# circuit.net
KiCad netlist of a schematic drawn in EAGLE
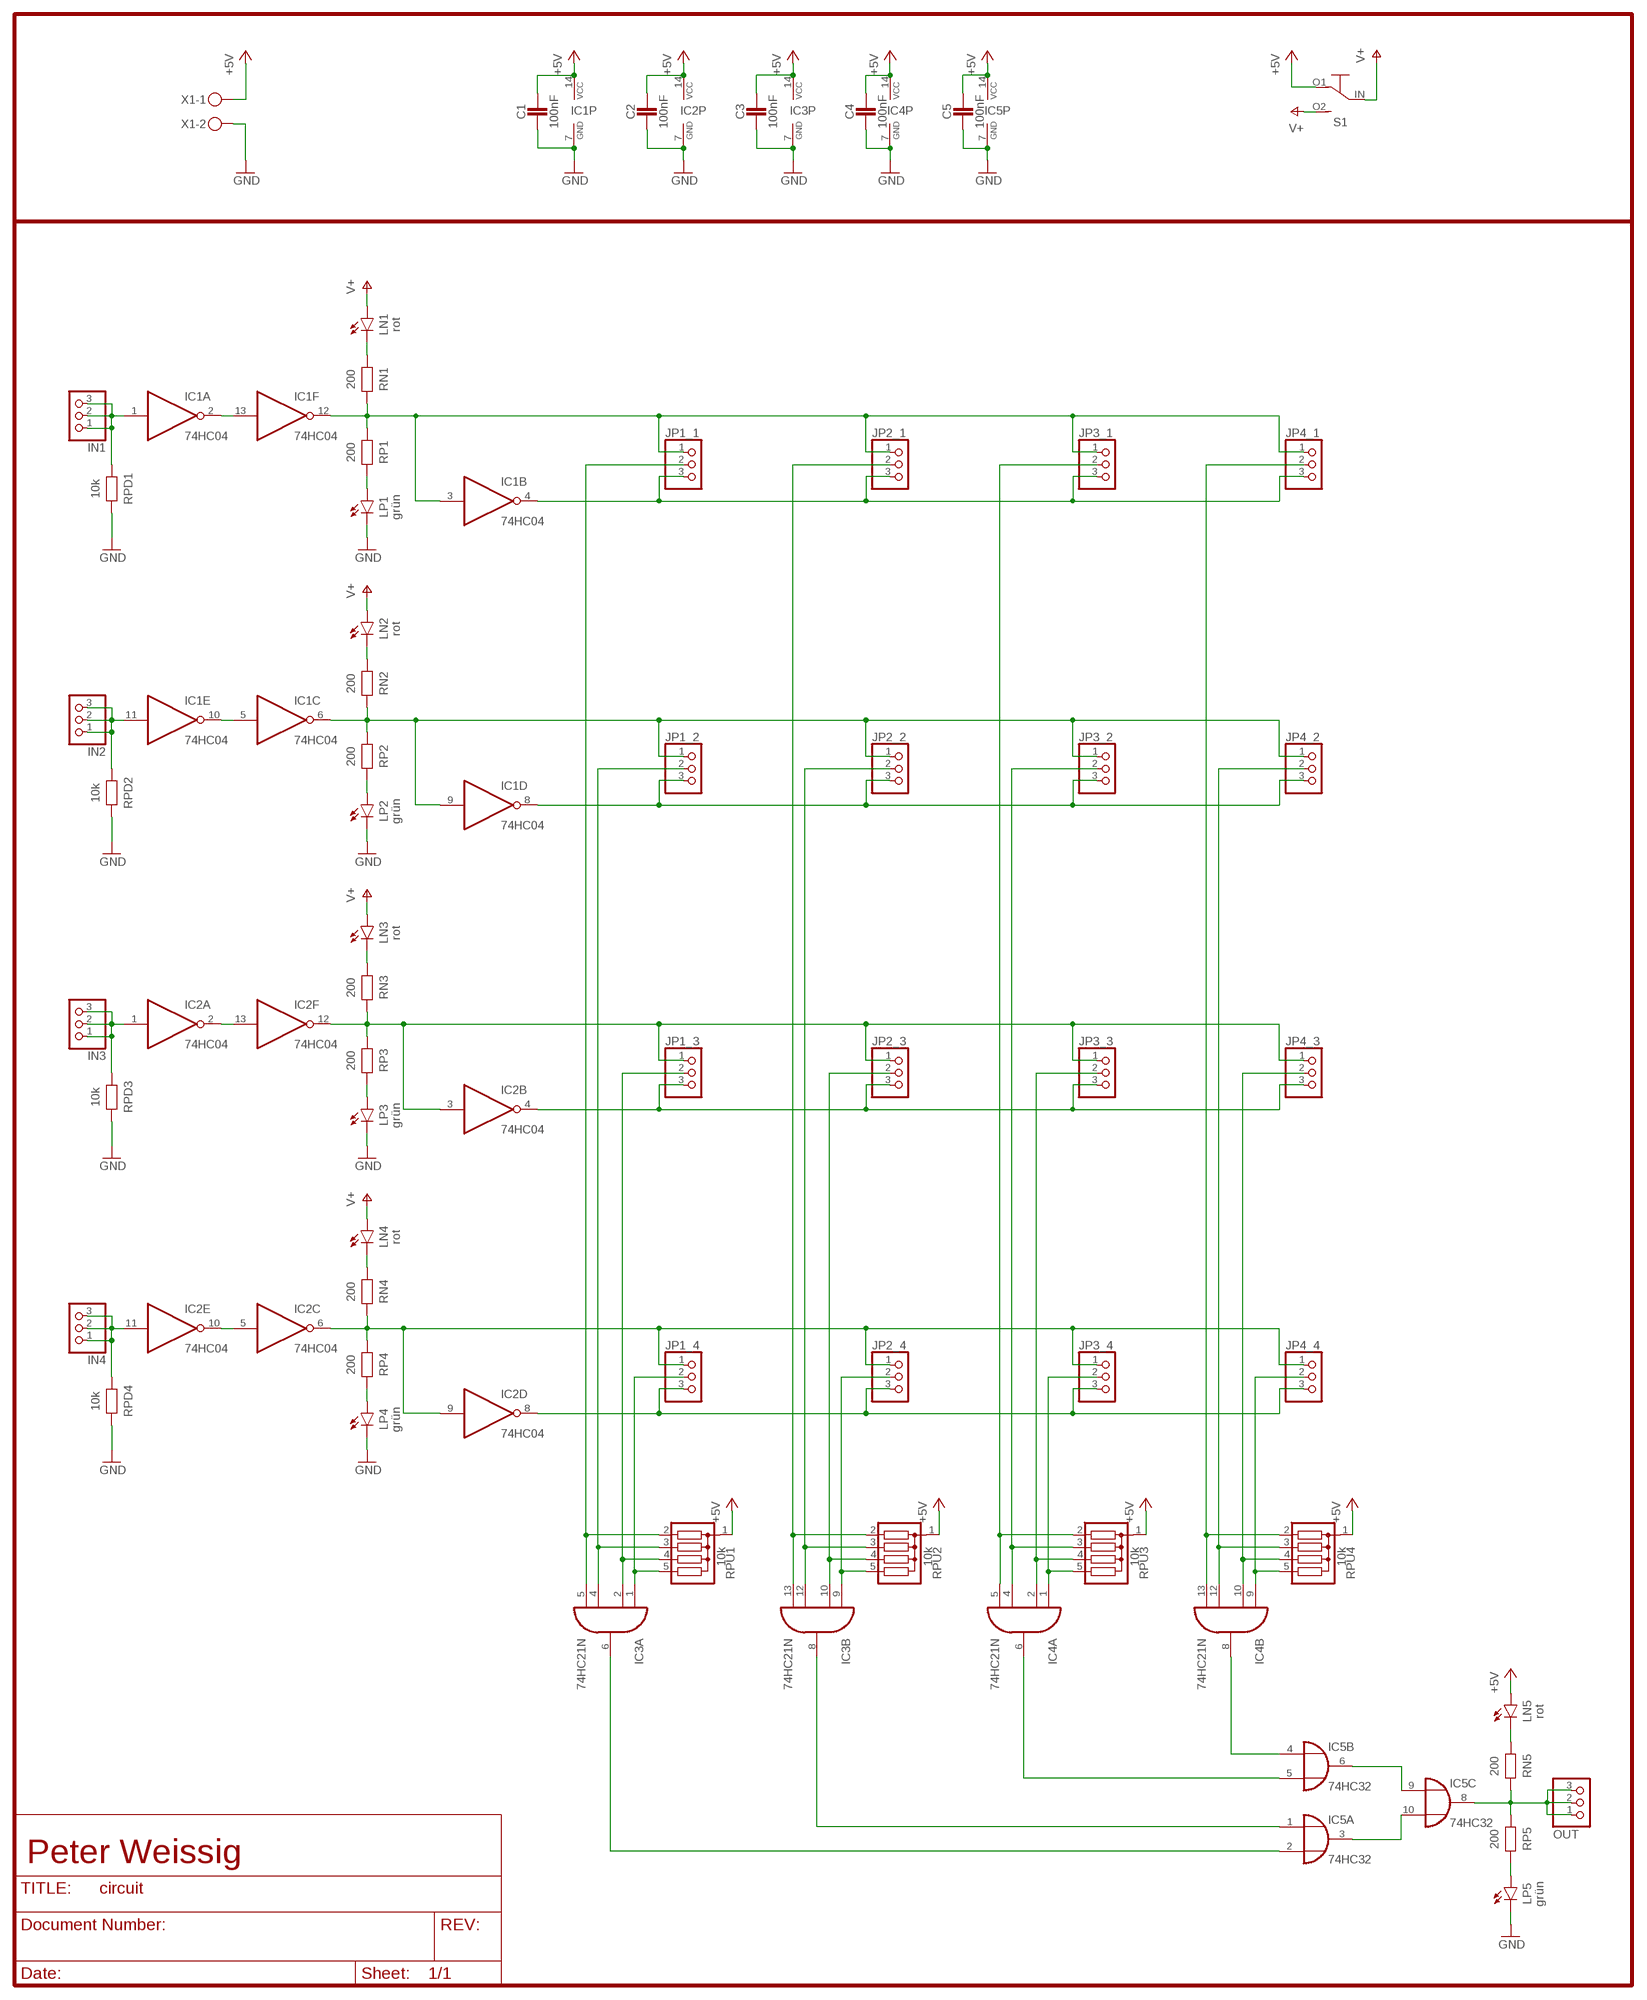
[diagram p0: schematic, sheet 1]

(export (version "E")
  (design (tool "Eeschema 10.0.6"))
  (components
    (comp (ref "C1")
      (value "100nF")
      (footprint "eagle-import:C_THT_2")
      (libsource (lib "eagle-import") (part "CAPACITATOR-2,5MM"))
    )
    (comp (ref "C2")
      (value "100nF")
      (footprint "eagle-import:C_THT_2")
      (libsource (lib "eagle-import") (part "CAPACITATOR-2,5MM"))
    )
    (comp (ref "C3")
      (value "100nF")
      (footprint "eagle-import:C_THT_3")
      (libsource (lib "eagle-import") (part "CAPACITATOR-5MM"))
    )
    (comp (ref "C4")
      (value "100nF")
      (footprint "eagle-import:C_THT_3")
      (libsource (lib "eagle-import") (part "CAPACITATOR-5MM"))
    )
    (comp (ref "C5")
      (value "100nF")
      (footprint "eagle-import:C_THT_2")
      (libsource (lib "eagle-import") (part "CAPACITATOR-2,5MM"))
    )
    (comp (ref "IC1")
      (value "74HC04")
      (footprint "eagle-import:DIL14")
      (libsource (lib "eagle-import") (part "7404NAC"))
    )
    (comp (ref "IC2")
      (value "74HC04")
      (footprint "eagle-import:DIL14")
      (libsource (lib "eagle-import") (part "7404NAC"))
    )
    (comp (ref "IC3")
      (value "74HC21N")
      (footprint "eagle-import:DIL14")
      (libsource (lib "eagle-import") (part "7421NHC"))
    )
    (comp (ref "IC4")
      (value "74HC21N")
      (footprint "eagle-import:DIL14")
      (libsource (lib "eagle-import") (part "7421NHC"))
    )
    (comp (ref "IC5")
      (value "74HC32")
      (footprint "eagle-import:DIL14")
      (libsource (lib "eagle-import") (part "7432NAC"))
    )
    (comp (ref "IN1")
      (value "PINHD-1X3")
      (footprint "eagle-import:1X03")
      (libsource (lib "eagle-import") (part "PINHD-1X3"))
    )
    (comp (ref "IN2")
      (value "PINHD-1X3")
      (footprint "eagle-import:1X03")
      (libsource (lib "eagle-import") (part "PINHD-1X3"))
    )
    (comp (ref "IN3")
      (value "PINHD-1X3")
      (footprint "eagle-import:1X03")
      (libsource (lib "eagle-import") (part "PINHD-1X3"))
    )
    (comp (ref "IN4")
      (value "PINHD-1X3")
      (footprint "eagle-import:1X03")
      (libsource (lib "eagle-import") (part "PINHD-1X3"))
    )
    (comp (ref "JP1_1")
      (value "PINHD-1X3")
      (footprint "eagle-import:1X03")
      (libsource (lib "eagle-import") (part "PINHD-1X3"))
    )
    (comp (ref "JP1_2")
      (value "PINHD-1X3")
      (footprint "eagle-import:1X03")
      (libsource (lib "eagle-import") (part "PINHD-1X3"))
    )
    (comp (ref "JP1_3")
      (value "PINHD-1X3")
      (footprint "eagle-import:1X03")
      (libsource (lib "eagle-import") (part "PINHD-1X3"))
    )
    (comp (ref "JP1_4")
      (value "PINHD-1X3")
      (footprint "eagle-import:1X03")
      (libsource (lib "eagle-import") (part "PINHD-1X3"))
    )
    (comp (ref "JP2_1")
      (value "PINHD-1X3")
      (footprint "eagle-import:1X03")
      (libsource (lib "eagle-import") (part "PINHD-1X3"))
    )
    (comp (ref "JP2_2")
      (value "PINHD-1X3")
      (footprint "eagle-import:1X03")
      (libsource (lib "eagle-import") (part "PINHD-1X3"))
    )
    (comp (ref "JP2_3")
      (value "PINHD-1X3")
      (footprint "eagle-import:1X03")
      (libsource (lib "eagle-import") (part "PINHD-1X3"))
    )
    (comp (ref "JP2_4")
      (value "PINHD-1X3")
      (footprint "eagle-import:1X03")
      (libsource (lib "eagle-import") (part "PINHD-1X3"))
    )
    (comp (ref "JP3_1")
      (value "PINHD-1X3")
      (footprint "eagle-import:1X03")
      (libsource (lib "eagle-import") (part "PINHD-1X3"))
    )
    (comp (ref "JP3_2")
      (value "PINHD-1X3")
      (footprint "eagle-import:1X03")
      (libsource (lib "eagle-import") (part "PINHD-1X3"))
    )
    (comp (ref "JP3_3")
      (value "PINHD-1X3")
      (footprint "eagle-import:1X03")
      (libsource (lib "eagle-import") (part "PINHD-1X3"))
    )
    (comp (ref "JP3_4")
      (value "PINHD-1X3")
      (footprint "eagle-import:1X03")
      (libsource (lib "eagle-import") (part "PINHD-1X3"))
    )
    (comp (ref "JP4_1")
      (value "PINHD-1X3")
      (footprint "eagle-import:1X03")
      (libsource (lib "eagle-import") (part "PINHD-1X3"))
    )
    (comp (ref "JP4_2")
      (value "PINHD-1X3")
      (footprint "eagle-import:1X03")
      (libsource (lib "eagle-import") (part "PINHD-1X3"))
    )
    (comp (ref "JP4_3")
      (value "PINHD-1X3")
      (footprint "eagle-import:1X03")
      (libsource (lib "eagle-import") (part "PINHD-1X3"))
    )
    (comp (ref "JP4_4")
      (value "PINHD-1X3")
      (footprint "eagle-import:1X03")
      (libsource (lib "eagle-import") (part "PINHD-1X3"))
    )
    (comp (ref "LN1")
      (value "rot")
      (footprint "eagle-import:LED_3MM")
      (libsource (lib "eagle-import") (part "LED-3MM"))
    )
    (comp (ref "LN2")
      (value "rot")
      (footprint "eagle-import:LED_3MM")
      (libsource (lib "eagle-import") (part "LED-3MM"))
    )
    (comp (ref "LN3")
      (value "rot")
      (footprint "eagle-import:LED_3MM")
      (libsource (lib "eagle-import") (part "LED-3MM"))
    )
    (comp (ref "LN4")
      (value "rot")
      (footprint "eagle-import:LED_3MM")
      (libsource (lib "eagle-import") (part "LED-3MM"))
    )
    (comp (ref "LN5")
      (value "rot")
      (footprint "eagle-import:LED_3MM")
      (libsource (lib "eagle-import") (part "LED-3MM"))
    )
    (comp (ref "LP1")
      (value "grün")
      (footprint "eagle-import:LED_3MM")
      (libsource (lib "eagle-import") (part "LED-3MM"))
    )
    (comp (ref "LP2")
      (value "grün")
      (footprint "eagle-import:LED_3MM")
      (libsource (lib "eagle-import") (part "LED-3MM"))
    )
    (comp (ref "LP3")
      (value "grün")
      (footprint "eagle-import:LED_3MM")
      (libsource (lib "eagle-import") (part "LED-3MM"))
    )
    (comp (ref "LP4")
      (value "grün")
      (footprint "eagle-import:LED_3MM")
      (libsource (lib "eagle-import") (part "LED-3MM"))
    )
    (comp (ref "LP5")
      (value "grün")
      (footprint "eagle-import:LED_3MM")
      (libsource (lib "eagle-import") (part "LED-3MM"))
    )
    (comp (ref "OUT")
      (value "PINHD-1X3")
      (footprint "eagle-import:1X03")
      (libsource (lib "eagle-import") (part "PINHD-1X3"))
    )
    (comp (ref "RN1")
      (value "200")
      (footprint "eagle-import:R_THT_4")
      (libsource (lib "eagle-import") (part "RESISTOR-10MM"))
    )
    (comp (ref "RN2")
      (value "200")
      (footprint "eagle-import:R_THT_4")
      (libsource (lib "eagle-import") (part "RESISTOR-10MM"))
    )
    (comp (ref "RN3")
      (value "200")
      (footprint "eagle-import:R_THT_4")
      (libsource (lib "eagle-import") (part "RESISTOR-10MM"))
    )
    (comp (ref "RN4")
      (value "200")
      (footprint "eagle-import:R_THT_4")
      (libsource (lib "eagle-import") (part "RESISTOR-10MM"))
    )
    (comp (ref "RN5")
      (value "200")
      (footprint "eagle-import:R_THT_4")
      (libsource (lib "eagle-import") (part "RESISTOR-10MM"))
    )
    (comp (ref "RP1")
      (value "200")
      (footprint "eagle-import:R_THT_4")
      (libsource (lib "eagle-import") (part "RESISTOR-10MM"))
    )
    (comp (ref "RP2")
      (value "200")
      (footprint "eagle-import:R_THT_4")
      (libsource (lib "eagle-import") (part "RESISTOR-10MM"))
    )
    (comp (ref "RP3")
      (value "200")
      (footprint "eagle-import:R_THT_4")
      (libsource (lib "eagle-import") (part "RESISTOR-10MM"))
    )
    (comp (ref "RP4")
      (value "200")
      (footprint "eagle-import:R_THT_4")
      (libsource (lib "eagle-import") (part "RESISTOR-10MM"))
    )
    (comp (ref "RP5")
      (value "200")
      (footprint "eagle-import:R_THT_4")
      (libsource (lib "eagle-import") (part "RESISTOR-10MM"))
    )
    (comp (ref "RPD1")
      (value "10k")
      (footprint "eagle-import:R_THT_4")
      (libsource (lib "eagle-import") (part "RESISTOR-10MM"))
    )
    (comp (ref "RPD2")
      (value "10k")
      (footprint "eagle-import:R_THT_4")
      (libsource (lib "eagle-import") (part "RESISTOR-10MM"))
    )
    (comp (ref "RPD3")
      (value "10k")
      (footprint "eagle-import:R_THT_4")
      (libsource (lib "eagle-import") (part "RESISTOR-10MM"))
    )
    (comp (ref "RPD4")
      (value "10k")
      (footprint "eagle-import:R_THT_4")
      (libsource (lib "eagle-import") (part "RESISTOR-10MM"))
    )
    (comp (ref "RPU1")
      (value "10k")
      (footprint "eagle-import:SIL5")
      (libsource (lib "eagle-import") (part "G04R"))
    )
    (comp (ref "RPU2")
      (value "10k")
      (footprint "eagle-import:SIL5")
      (libsource (lib "eagle-import") (part "G04R"))
    )
    (comp (ref "RPU3")
      (value "10k")
      (footprint "eagle-import:SIL5")
      (libsource (lib "eagle-import") (part "G04R"))
    )
    (comp (ref "RPU4")
      (value "10k")
      (footprint "eagle-import:SIL5")
      (libsource (lib "eagle-import") (part "G04R"))
    )
    (comp (ref "S1")
      (value "SCHALTER_UM-KIPP")
      (footprint "eagle-import:SCHALTER_KIPP_UM")
      (libsource (lib "eagle-import") (part "SCHALTER_UM-KIPP"))
    )
    (comp (ref "X1")
      (value "STECKER_SPG_2")
      (footprint "eagle-import:STECKER_SPG_2")
      (libsource (lib "eagle-import") (part "STECKER_SPG_2"))
    )
  )
  (nets
    (net (code "1") (name "+5V") (class "Default")
      (node (ref "C1") (pin "1") (pinfunction "1_1") (pintype "passive"))
      (node (ref "C2") (pin "1") (pinfunction "1_1") (pintype "passive"))
      (node (ref "C3") (pin "1") (pinfunction "1_1") (pintype "passive"))
      (node (ref "C4") (pin "1") (pinfunction "1_1") (pintype "passive"))
      (node (ref "C5") (pin "1") (pinfunction "1_1") (pintype "passive"))
      (node (ref "IC1") (pin "14") (pinfunction "VCC_14") (pintype "power_in"))
      (node (ref "IC2") (pin "14") (pinfunction "VCC_14") (pintype "power_in"))
      (node (ref "IC3") (pin "14") (pinfunction "VCC_14") (pintype "power_in"))
      (node (ref "IC4") (pin "14") (pinfunction "VCC_14") (pintype "power_in"))
      (node (ref "IC5") (pin "14") (pinfunction "VCC_14") (pintype "power_in"))
      (node (ref "LN5") (pin "A") (pinfunction "A_A") (pintype "passive"))
      (node (ref "RPU1") (pin "1") (pinfunction "1_1") (pintype "passive"))
      (node (ref "RPU2") (pin "1") (pinfunction "1_1") (pintype "passive"))
      (node (ref "RPU3") (pin "1") (pinfunction "1_1") (pintype "passive"))
      (node (ref "RPU4") (pin "1") (pinfunction "1_1") (pintype "passive"))
      (node (ref "S1") (pin "O1") (pinfunction "O1_O1") (pintype "passive"))
      (node (ref "X1") (pin "1") (pinfunction "KL_1") (pintype "passive"))
    )
    (net (code "2") (name "GND") (class "Default")
      (node (ref "C1") (pin "2") (pinfunction "2_2") (pintype "passive"))
      (node (ref "C2") (pin "2") (pinfunction "2_2") (pintype "passive"))
      (node (ref "C3") (pin "2") (pinfunction "2_2") (pintype "passive"))
      (node (ref "C4") (pin "2") (pinfunction "2_2") (pintype "passive"))
      (node (ref "C5") (pin "2") (pinfunction "2_2") (pintype "passive"))
      (node (ref "IC1") (pin "7") (pinfunction "GND_7") (pintype "power_in"))
      (node (ref "IC2") (pin "7") (pinfunction "GND_7") (pintype "power_in"))
      (node (ref "IC3") (pin "7") (pinfunction "GND_7") (pintype "power_in"))
      (node (ref "IC4") (pin "7") (pinfunction "GND_7") (pintype "power_in"))
      (node (ref "IC5") (pin "7") (pinfunction "GND_7") (pintype "power_in"))
      (node (ref "LP1") (pin "K") (pinfunction "C_K") (pintype "passive"))
      (node (ref "LP2") (pin "K") (pinfunction "C_K") (pintype "passive"))
      (node (ref "LP3") (pin "K") (pinfunction "C_K") (pintype "passive"))
      (node (ref "LP4") (pin "K") (pinfunction "C_K") (pintype "passive"))
      (node (ref "LP5") (pin "K") (pinfunction "C_K") (pintype "passive"))
      (node (ref "RPD1") (pin "1") (pinfunction "P1_1") (pintype "passive"))
      (node (ref "RPD2") (pin "1") (pinfunction "P1_1") (pintype "passive"))
      (node (ref "RPD3") (pin "1") (pinfunction "P1_1") (pintype "passive"))
      (node (ref "RPD4") (pin "1") (pinfunction "P1_1") (pintype "passive"))
      (node (ref "X1") (pin "2") (pinfunction "KL_2") (pintype "passive"))
    )
    (net (code "3") (name "Net-(IC1A-I)") (class "Default")
      (node (ref "IC1") (pin "1") (pinfunction "I_1") (pintype "input"))
      (node (ref "IN1") (pin "1") (pinfunction "1_1") (pintype "passive"))
      (node (ref "IN1") (pin "2") (pinfunction "2_2") (pintype "passive"))
      (node (ref "IN1") (pin "3") (pinfunction "3_3") (pintype "passive"))
      (node (ref "RPD1") (pin "2") (pinfunction "P2_2") (pintype "passive"))
    )
    (net (code "4") (name "Net-(IC1A-O)") (class "Default")
      (node (ref "IC1") (pin "13") (pinfunction "I_13") (pintype "input"))
      (node (ref "IC1") (pin "2") (pinfunction "O_2") (pintype "output"))
    )
    (net (code "5") (name "Net-(IC1B-I)") (class "Default")
      (node (ref "IC1") (pin "12") (pinfunction "O_12") (pintype "output"))
      (node (ref "IC1") (pin "3") (pinfunction "I_3") (pintype "input"))
      (node (ref "JP1_1") (pin "1") (pinfunction "1_1") (pintype "passive"))
      (node (ref "JP2_1") (pin "1") (pinfunction "1_1") (pintype "passive"))
      (node (ref "JP3_1") (pin "1") (pinfunction "1_1") (pintype "passive"))
      (node (ref "JP4_1") (pin "1") (pinfunction "1_1") (pintype "passive"))
      (node (ref "RN1") (pin "1") (pinfunction "P1_1") (pintype "passive"))
      (node (ref "RP1") (pin "2") (pinfunction "P2_2") (pintype "passive"))
    )
    (net (code "6") (name "Net-(IC1B-O)") (class "Default")
      (node (ref "IC1") (pin "4") (pinfunction "O_4") (pintype "output"))
      (node (ref "JP1_1") (pin "3") (pinfunction "3_3") (pintype "passive"))
      (node (ref "JP2_1") (pin "3") (pinfunction "3_3") (pintype "passive"))
      (node (ref "JP3_1") (pin "3") (pinfunction "3_3") (pintype "passive"))
      (node (ref "JP4_1") (pin "3") (pinfunction "3_3") (pintype "passive"))
    )
    (net (code "7") (name "Net-(IC1C-I)") (class "Default")
      (node (ref "IC1") (pin "10") (pinfunction "O_10") (pintype "output"))
      (node (ref "IC1") (pin "5") (pinfunction "I_5") (pintype "input"))
    )
    (net (code "8") (name "Net-(IC1C-O)") (class "Default")
      (node (ref "IC1") (pin "6") (pinfunction "O_6") (pintype "output"))
      (node (ref "IC1") (pin "9") (pinfunction "I_9") (pintype "input"))
      (node (ref "JP1_2") (pin "1") (pinfunction "1_1") (pintype "passive"))
      (node (ref "JP2_2") (pin "1") (pinfunction "1_1") (pintype "passive"))
      (node (ref "JP3_2") (pin "1") (pinfunction "1_1") (pintype "passive"))
      (node (ref "JP4_2") (pin "1") (pinfunction "1_1") (pintype "passive"))
      (node (ref "RN2") (pin "1") (pinfunction "P1_1") (pintype "passive"))
      (node (ref "RP2") (pin "2") (pinfunction "P2_2") (pintype "passive"))
    )
    (net (code "9") (name "Net-(IC1D-O)") (class "Default")
      (node (ref "IC1") (pin "8") (pinfunction "O_8") (pintype "output"))
      (node (ref "JP1_2") (pin "3") (pinfunction "3_3") (pintype "passive"))
      (node (ref "JP2_2") (pin "3") (pinfunction "3_3") (pintype "passive"))
      (node (ref "JP3_2") (pin "3") (pinfunction "3_3") (pintype "passive"))
      (node (ref "JP4_2") (pin "3") (pinfunction "3_3") (pintype "passive"))
    )
    (net (code "10") (name "Net-(IC1E-I)") (class "Default")
      (node (ref "IC1") (pin "11") (pinfunction "I_11") (pintype "input"))
      (node (ref "IN2") (pin "1") (pinfunction "1_1") (pintype "passive"))
      (node (ref "IN2") (pin "2") (pinfunction "2_2") (pintype "passive"))
      (node (ref "IN2") (pin "3") (pinfunction "3_3") (pintype "passive"))
      (node (ref "RPD2") (pin "2") (pinfunction "P2_2") (pintype "passive"))
    )
    (net (code "11") (name "Net-(IC2A-I)") (class "Default")
      (node (ref "IC2") (pin "1") (pinfunction "I_1") (pintype "input"))
      (node (ref "IN3") (pin "1") (pinfunction "1_1") (pintype "passive"))
      (node (ref "IN3") (pin "2") (pinfunction "2_2") (pintype "passive"))
      (node (ref "IN3") (pin "3") (pinfunction "3_3") (pintype "passive"))
      (node (ref "RPD3") (pin "2") (pinfunction "P2_2") (pintype "passive"))
    )
    (net (code "12") (name "Net-(IC2A-O)") (class "Default")
      (node (ref "IC2") (pin "13") (pinfunction "I_13") (pintype "input"))
      (node (ref "IC2") (pin "2") (pinfunction "O_2") (pintype "output"))
    )
    (net (code "13") (name "Net-(IC2B-I)") (class "Default")
      (node (ref "IC2") (pin "12") (pinfunction "O_12") (pintype "output"))
      (node (ref "IC2") (pin "3") (pinfunction "I_3") (pintype "input"))
      (node (ref "JP1_3") (pin "1") (pinfunction "1_1") (pintype "passive"))
      (node (ref "JP2_3") (pin "1") (pinfunction "1_1") (pintype "passive"))
      (node (ref "JP3_3") (pin "1") (pinfunction "1_1") (pintype "passive"))
      (node (ref "JP4_3") (pin "1") (pinfunction "1_1") (pintype "passive"))
      (node (ref "RN3") (pin "1") (pinfunction "P1_1") (pintype "passive"))
      (node (ref "RP3") (pin "2") (pinfunction "P2_2") (pintype "passive"))
    )
    (net (code "14") (name "Net-(IC2B-O)") (class "Default")
      (node (ref "IC2") (pin "4") (pinfunction "O_4") (pintype "output"))
      (node (ref "JP1_3") (pin "3") (pinfunction "3_3") (pintype "passive"))
      (node (ref "JP2_3") (pin "3") (pinfunction "3_3") (pintype "passive"))
      (node (ref "JP3_3") (pin "3") (pinfunction "3_3") (pintype "passive"))
      (node (ref "JP4_3") (pin "3") (pinfunction "3_3") (pintype "passive"))
    )
    (net (code "15") (name "Net-(IC2C-I)") (class "Default")
      (node (ref "IC2") (pin "10") (pinfunction "O_10") (pintype "output"))
      (node (ref "IC2") (pin "5") (pinfunction "I_5") (pintype "input"))
    )
    (net (code "16") (name "Net-(IC2C-O)") (class "Default")
      (node (ref "IC2") (pin "6") (pinfunction "O_6") (pintype "output"))
      (node (ref "IC2") (pin "9") (pinfunction "I_9") (pintype "input"))
      (node (ref "JP1_4") (pin "1") (pinfunction "1_1") (pintype "passive"))
      (node (ref "JP2_4") (pin "1") (pinfunction "1_1") (pintype "passive"))
      (node (ref "JP3_4") (pin "1") (pinfunction "1_1") (pintype "passive"))
      (node (ref "JP4_4") (pin "1") (pinfunction "1_1") (pintype "passive"))
      (node (ref "RN4") (pin "1") (pinfunction "P1_1") (pintype "passive"))
      (node (ref "RP4") (pin "2") (pinfunction "P2_2") (pintype "passive"))
    )
    (net (code "17") (name "Net-(IC2D-O)") (class "Default")
      (node (ref "IC2") (pin "8") (pinfunction "O_8") (pintype "output"))
      (node (ref "JP1_4") (pin "3") (pinfunction "3_3") (pintype "passive"))
      (node (ref "JP2_4") (pin "3") (pinfunction "3_3") (pintype "passive"))
      (node (ref "JP3_4") (pin "3") (pinfunction "3_3") (pintype "passive"))
      (node (ref "JP4_4") (pin "3") (pinfunction "3_3") (pintype "passive"))
    )
    (net (code "18") (name "Net-(IC2E-I)") (class "Default")
      (node (ref "IC2") (pin "11") (pinfunction "I_11") (pintype "input"))
      (node (ref "IN4") (pin "1") (pinfunction "1_1") (pintype "passive"))
      (node (ref "IN4") (pin "2") (pinfunction "2_2") (pintype "passive"))
      (node (ref "IN4") (pin "3") (pinfunction "3_3") (pintype "passive"))
      (node (ref "RPD4") (pin "2") (pinfunction "P2_2") (pintype "passive"))
    )
    (net (code "19") (name "Net-(IC3A-I0)") (class "Default")
      (node (ref "IC3") (pin "1") (pinfunction "I0_1") (pintype "input"))
      (node (ref "JP1_4") (pin "2") (pinfunction "2_2") (pintype "passive"))
      (node (ref "RPU1") (pin "5") (pinfunction "5_5") (pintype "passive"))
    )
    (net (code "20") (name "Net-(IC3A-I1)") (class "Default")
      (node (ref "IC3") (pin "2") (pinfunction "I1_2") (pintype "input"))
      (node (ref "JP1_3") (pin "2") (pinfunction "2_2") (pintype "passive"))
      (node (ref "RPU1") (pin "4") (pinfunction "4_4") (pintype "passive"))
    )
    (net (code "21") (name "Net-(IC3A-I2)") (class "Default")
      (node (ref "IC3") (pin "4") (pinfunction "I2_4") (pintype "input"))
      (node (ref "JP1_2") (pin "2") (pinfunction "2_2") (pintype "passive"))
      (node (ref "RPU1") (pin "3") (pinfunction "3_3") (pintype "passive"))
    )
    (net (code "22") (name "Net-(IC3A-I3)") (class "Default")
      (node (ref "IC3") (pin "5") (pinfunction "I3_5") (pintype "input"))
      (node (ref "JP1_1") (pin "2") (pinfunction "2_2") (pintype "passive"))
      (node (ref "RPU1") (pin "2") (pinfunction "2_2") (pintype "passive"))
    )
    (net (code "23") (name "Net-(IC3A-O)") (class "Default")
      (node (ref "IC3") (pin "6") (pinfunction "O_6") (pintype "output"))
      (node (ref "IC5") (pin "2") (pinfunction "I1_2") (pintype "input"))
    )
    (net (code "24") (name "Net-(IC3B-I0)") (class "Default")
      (node (ref "IC3") (pin "9") (pinfunction "I0_9") (pintype "input"))
      (node (ref "JP2_4") (pin "2") (pinfunction "2_2") (pintype "passive"))
      (node (ref "RPU2") (pin "5") (pinfunction "5_5") (pintype "passive"))
    )
    (net (code "25") (name "Net-(IC3B-I1)") (class "Default")
      (node (ref "IC3") (pin "10") (pinfunction "I1_10") (pintype "input"))
      (node (ref "JP2_3") (pin "2") (pinfunction "2_2") (pintype "passive"))
      (node (ref "RPU2") (pin "4") (pinfunction "4_4") (pintype "passive"))
    )
    (net (code "26") (name "Net-(IC3B-I2)") (class "Default")
      (node (ref "IC3") (pin "12") (pinfunction "I2_12") (pintype "input"))
      (node (ref "JP2_2") (pin "2") (pinfunction "2_2") (pintype "passive"))
      (node (ref "RPU2") (pin "3") (pinfunction "3_3") (pintype "passive"))
    )
    (net (code "27") (name "Net-(IC3B-I3)") (class "Default")
      (node (ref "IC3") (pin "13") (pinfunction "I3_13") (pintype "input"))
      (node (ref "JP2_1") (pin "2") (pinfunction "2_2") (pintype "passive"))
      (node (ref "RPU2") (pin "2") (pinfunction "2_2") (pintype "passive"))
    )
    (net (code "28") (name "Net-(IC3B-O)") (class "Default")
      (node (ref "IC3") (pin "8") (pinfunction "O_8") (pintype "output"))
      (node (ref "IC5") (pin "1") (pinfunction "I0_1") (pintype "input"))
    )
    (net (code "29") (name "Net-(IC4A-I0)") (class "Default")
      (node (ref "IC4") (pin "1") (pinfunction "I0_1") (pintype "input"))
      (node (ref "JP3_4") (pin "2") (pinfunction "2_2") (pintype "passive"))
      (node (ref "RPU3") (pin "5") (pinfunction "5_5") (pintype "passive"))
    )
    (net (code "30") (name "Net-(IC4A-I1)") (class "Default")
      (node (ref "IC4") (pin "2") (pinfunction "I1_2") (pintype "input"))
      (node (ref "JP3_3") (pin "2") (pinfunction "2_2") (pintype "passive"))
      (node (ref "RPU3") (pin "4") (pinfunction "4_4") (pintype "passive"))
    )
    (net (code "31") (name "Net-(IC4A-I2)") (class "Default")
      (node (ref "IC4") (pin "4") (pinfunction "I2_4") (pintype "input"))
      (node (ref "JP3_2") (pin "2") (pinfunction "2_2") (pintype "passive"))
      (node (ref "RPU3") (pin "3") (pinfunction "3_3") (pintype "passive"))
    )
    (net (code "32") (name "Net-(IC4A-I3)") (class "Default")
      (node (ref "IC4") (pin "5") (pinfunction "I3_5") (pintype "input"))
      (node (ref "JP3_1") (pin "2") (pinfunction "2_2") (pintype "passive"))
      (node (ref "RPU3") (pin "2") (pinfunction "2_2") (pintype "passive"))
    )
    (net (code "33") (name "Net-(IC4A-O)") (class "Default")
      (node (ref "IC4") (pin "6") (pinfunction "O_6") (pintype "output"))
      (node (ref "IC5") (pin "5") (pinfunction "I1_5") (pintype "input"))
    )
    (net (code "34") (name "Net-(IC4B-I0)") (class "Default")
      (node (ref "IC4") (pin "9") (pinfunction "I0_9") (pintype "input"))
      (node (ref "JP4_4") (pin "2") (pinfunction "2_2") (pintype "passive"))
      (node (ref "RPU4") (pin "5") (pinfunction "5_5") (pintype "passive"))
    )
    (net (code "35") (name "Net-(IC4B-I1)") (class "Default")
      (node (ref "IC4") (pin "10") (pinfunction "I1_10") (pintype "input"))
      (node (ref "JP4_3") (pin "2") (pinfunction "2_2") (pintype "passive"))
      (node (ref "RPU4") (pin "4") (pinfunction "4_4") (pintype "passive"))
    )
    (net (code "36") (name "Net-(IC4B-I2)") (class "Default")
      (node (ref "IC4") (pin "12") (pinfunction "I2_12") (pintype "input"))
      (node (ref "JP4_2") (pin "2") (pinfunction "2_2") (pintype "passive"))
      (node (ref "RPU4") (pin "3") (pinfunction "3_3") (pintype "passive"))
    )
    (net (code "37") (name "Net-(IC4B-I3)") (class "Default")
      (node (ref "IC4") (pin "13") (pinfunction "I3_13") (pintype "input"))
      (node (ref "JP4_1") (pin "2") (pinfunction "2_2") (pintype "passive"))
      (node (ref "RPU4") (pin "2") (pinfunction "2_2") (pintype "passive"))
    )
    (net (code "38") (name "Net-(IC4B-O)") (class "Default")
      (node (ref "IC4") (pin "8") (pinfunction "O_8") (pintype "output"))
      (node (ref "IC5") (pin "4") (pinfunction "I0_4") (pintype "input"))
    )
    (net (code "39") (name "Net-(IC5A-O)") (class "Default")
      (node (ref "IC5") (pin "10") (pinfunction "I1_10") (pintype "input"))
      (node (ref "IC5") (pin "3") (pinfunction "O_3") (pintype "output"))
    )
    (net (code "40") (name "Net-(IC5B-O)") (class "Default")
      (node (ref "IC5") (pin "6") (pinfunction "O_6") (pintype "output"))
      (node (ref "IC5") (pin "9") (pinfunction "I0_9") (pintype "input"))
    )
    (net (code "41") (name "Net-(IC5C-O)") (class "Default")
      (node (ref "IC5") (pin "8") (pinfunction "O_8") (pintype "output"))
      (node (ref "OUT") (pin "1") (pinfunction "1_1") (pintype "passive"))
      (node (ref "OUT") (pin "2") (pinfunction "2_2") (pintype "passive"))
      (node (ref "OUT") (pin "3") (pinfunction "3_3") (pintype "passive"))
      (node (ref "RN5") (pin "1") (pinfunction "P1_1") (pintype "passive"))
      (node (ref "RP5") (pin "2") (pinfunction "P2_2") (pintype "passive"))
    )
    (net (code "42") (name "Net-(LN1-C)") (class "Default")
      (node (ref "LN1") (pin "K") (pinfunction "C_K") (pintype "passive"))
      (node (ref "RN1") (pin "2") (pinfunction "P2_2") (pintype "passive"))
    )
    (net (code "43") (name "Net-(LN2-C)") (class "Default")
      (node (ref "LN2") (pin "K") (pinfunction "C_K") (pintype "passive"))
      (node (ref "RN2") (pin "2") (pinfunction "P2_2") (pintype "passive"))
    )
    (net (code "44") (name "Net-(LN3-C)") (class "Default")
      (node (ref "LN3") (pin "K") (pinfunction "C_K") (pintype "passive"))
      (node (ref "RN3") (pin "2") (pinfunction "P2_2") (pintype "passive"))
    )
    (net (code "45") (name "Net-(LN4-C)") (class "Default")
      (node (ref "LN4") (pin "K") (pinfunction "C_K") (pintype "passive"))
      (node (ref "RN4") (pin "2") (pinfunction "P2_2") (pintype "passive"))
    )
    (net (code "46") (name "Net-(LN5-C)") (class "Default")
      (node (ref "LN5") (pin "K") (pinfunction "C_K") (pintype "passive"))
      (node (ref "RN5") (pin "2") (pinfunction "P2_2") (pintype "passive"))
    )
    (net (code "47") (name "Net-(RP1-P1)") (class "Default")
      (node (ref "LP1") (pin "A") (pinfunction "A_A") (pintype "passive"))
      (node (ref "RP1") (pin "1") (pinfunction "P1_1") (pintype "passive"))
    )
    (net (code "48") (name "Net-(RP2-P1)") (class "Default")
      (node (ref "LP2") (pin "A") (pinfunction "A_A") (pintype "passive"))
      (node (ref "RP2") (pin "1") (pinfunction "P1_1") (pintype "passive"))
    )
    (net (code "49") (name "Net-(RP3-P1)") (class "Default")
      (node (ref "LP3") (pin "A") (pinfunction "A_A") (pintype "passive"))
      (node (ref "RP3") (pin "1") (pinfunction "P1_1") (pintype "passive"))
    )
    (net (code "50") (name "Net-(RP4-P1)") (class "Default")
      (node (ref "LP4") (pin "A") (pinfunction "A_A") (pintype "passive"))
      (node (ref "RP4") (pin "1") (pinfunction "P1_1") (pintype "passive"))
    )
    (net (code "51") (name "Net-(RP5-P1)") (class "Default")
      (node (ref "LP5") (pin "A") (pinfunction "A_A") (pintype "passive"))
      (node (ref "RP5") (pin "1") (pinfunction "P1_1") (pintype "passive"))
    )
    (net (code "52") (name "V+") (class "Default")
      (node (ref "LN1") (pin "A") (pinfunction "A_A") (pintype "passive"))
      (node (ref "LN2") (pin "A") (pinfunction "A_A") (pintype "passive"))
      (node (ref "LN3") (pin "A") (pinfunction "A_A") (pintype "passive"))
      (node (ref "LN4") (pin "A") (pinfunction "A_A") (pintype "passive"))
      (node (ref "S1") (pin "IN") (pinfunction "IN_IN") (pintype "passive"))
      (node (ref "S1") (pin "O2") (pinfunction "O2_O2") (pintype "passive"))
    )
  )
)
